# ra01m.net
KiCad netlist of a schematic drawn in Altium Designer
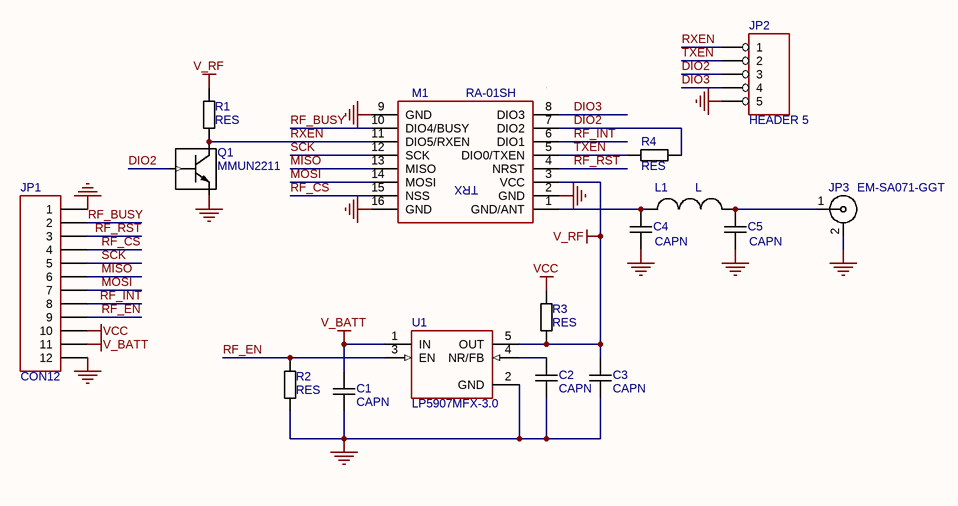
[diagram p0: ra01m.SchDoc]

(export (version "E")
  (design (tool "Eeschema 10.0.6"))
  (components
    (comp (ref "C1")
      (value "CAPN")
      (footprint "C-0805")
      (fields (field (name "VOLTAGE") "50V"))
      (libsource (lib "Passive") (part "CAPN"))
    )
    (comp (ref "C2")
      (value "CAPN")
      (footprint "C-0603")
      (fields (field (name "VOLTAGE") "50V"))
      (libsource (lib "Passive") (part "CAPN"))
    )
    (comp (ref "C3")
      (value "CAPN")
      (footprint "C-0805")
      (fields (field (name "VOLTAGE") "50V"))
      (libsource (lib "Passive") (part "CAPN"))
    )
    (comp (ref "C4")
      (value "CAPN")
      (footprint "C-0603")
      (fields (field (name "VOLTAGE") "50V"))
      (libsource (lib "Passive") (part "CAPN"))
    )
    (comp (ref "C5")
      (value "CAPN")
      (footprint "C-0603")
      (fields (field (name "VOLTAGE") "50V"))
      (libsource (lib "Passive") (part "CAPN"))
    )
    (comp (ref "JP1")
      (value "CON12")
      (footprint "PBS1-12R")
      (description "Connector")
      (libsource (lib "Connectors") (part "CON12"))
    )
    (comp (ref "JP2")
      (value "HEADER 5")
      (footprint "PLS1-5")
      (libsource (lib "Connectors") (part "HEADER 5"))
    )
    (comp (ref "JP3")
      (value "EM-SA071-GGT")
      (footprint "SMA_F_EDGE")
      (description "SMA Female R/A PCB Mount")
      (libsource (lib "Connectors") (part "SMA"))
    )
    (comp (ref "L1") (value "L") (footprint "L-0603") (libsource (lib "Passive") (part "L")))
    (comp (ref "M1")
      (value "RA-01SH")
      (footprint "RA01")
      (libsource (lib "RFmodules") (part "RA01_02_HT_RA_62"))
    )
    (comp (ref "Q1")
      (value "MMUN2211")
      (footprint "SOT-23")
      (libsource (lib "Transistors") (part "MMUN2211"))
    )
    (comp (ref "R1") (value "RES") (footprint "R-0603") (libsource (lib "Passive") (part "RES")))
    (comp (ref "R2") (value "RES") (footprint "R-0603") (libsource (lib "") (part "RES_1")))
    (comp (ref "R3") (value "RES") (footprint "R-0603") (libsource (lib "") (part "RES_1")))
    (comp (ref "R4") (value "RES") (footprint "R-0603") (libsource (lib "") (part "RES_2")))
    (comp (ref "U1")
      (value "LP5907MFX-3.0")
      (footprint "SOT-23-5")
      (description "250mA Low-Dropout Regulator")
      (libsource (lib "ICs") (part "LP5907"))
    )
  )
  (nets
    (net (code "1") (name "/DIO2") (class "Default")
      (node (ref "JP2") (pin "3") (pinfunction "3_3") (pintype "passive"))
      (node (ref "M1") (pin "7") (pinfunction "DIO2_7") (pintype "passive"))
      (node (ref "Q1") (pin "1") (pinfunction "BASE_1") (pintype "input"))
      (node (ref "R4") (pin "1") (pinfunction "1_1") (pintype "passive"))
    )
    (net (code "2") (name "/DIO3") (class "Default")
      (node (ref "JP2") (pin "4") (pinfunction "4_4") (pintype "passive"))
      (node (ref "M1") (pin "8") (pinfunction "DIO3_8") (pintype "passive"))
    )
    (net (code "3") (name "/MISO") (class "Default")
      (node (ref "JP1") (pin "6") (pinfunction "6_6") (pintype "passive"))
      (node (ref "M1") (pin "13") (pinfunction "MISO_13") (pintype "passive"))
    )
    (net (code "4") (name "/MOSI") (class "Default")
      (node (ref "JP1") (pin "7") (pinfunction "7_7") (pintype "passive"))
      (node (ref "M1") (pin "14") (pinfunction "MOSI_14") (pintype "passive"))
    )
    (net (code "5") (name "/RF_BUSY") (class "Default")
      (node (ref "JP1") (pin "2") (pinfunction "2_2") (pintype "passive"))
      (node (ref "M1") (pin "10") (pinfunction "DIO4/BUSY_10") (pintype "passive"))
    )
    (net (code "6") (name "/RF_CS") (class "Default")
      (node (ref "JP1") (pin "4") (pinfunction "4_4") (pintype "passive"))
      (node (ref "M1") (pin "15") (pinfunction "NSS_15") (pintype "passive"))
    )
    (net (code "7") (name "/RF_EN") (class "Default")
      (node (ref "JP1") (pin "9") (pinfunction "9_9") (pintype "passive"))
      (node (ref "R2") (pin "2") (pinfunction "2_2") (pintype "passive"))
      (node (ref "U1") (pin "3") (pinfunction "EN_3") (pintype "input"))
    )
    (net (code "8") (name "/RF_INT") (class "Default")
      (node (ref "JP1") (pin "8") (pinfunction "8_8") (pintype "passive"))
      (node (ref "M1") (pin "6") (pinfunction "DIO1_6") (pintype "passive"))
    )
    (net (code "9") (name "/RF_RST") (class "Default")
      (node (ref "JP1") (pin "3") (pinfunction "3_3") (pintype "passive"))
      (node (ref "M1") (pin "4") (pinfunction "NRST_4") (pintype "passive"))
    )
    (net (code "10") (name "/RXEN") (class "Default")
      (node (ref "JP2") (pin "1") (pinfunction "1_1") (pintype "passive"))
      (node (ref "M1") (pin "11") (pinfunction "DIO5/RXEN_11") (pintype "passive"))
      (node (ref "Q1") (pin "3") (pinfunction "COLLECTOR_3") (pintype "passive"))
      (node (ref "R1") (pin "2") (pinfunction "2_2") (pintype "passive"))
    )
    (net (code "11") (name "/SCK") (class "Default")
      (node (ref "JP1") (pin "5") (pinfunction "5_5") (pintype "passive"))
      (node (ref "M1") (pin "12") (pinfunction "SCK_12") (pintype "passive"))
    )
    (net (code "12") (name "/TXEN") (class "Default")
      (node (ref "JP2") (pin "2") (pinfunction "2_2") (pintype "passive"))
      (node (ref "M1") (pin "5") (pinfunction "DIO0/TXEN_5") (pintype "passive"))
      (node (ref "R4") (pin "2") (pinfunction "2_2") (pintype "passive"))
    )
    (net (code "13") (name "GND") (class "Default")
      (node (ref "C1") (pin "2") (pinfunction "2_2") (pintype "passive"))
      (node (ref "C2") (pin "2") (pinfunction "2_2") (pintype "passive"))
      (node (ref "C3") (pin "2") (pinfunction "2_2") (pintype "passive"))
      (node (ref "C4") (pin "2") (pinfunction "2_2") (pintype "passive"))
      (node (ref "C5") (pin "2") (pinfunction "2_2") (pintype "passive"))
      (node (ref "JP1") (pin "1") (pinfunction "1_1") (pintype "passive"))
      (node (ref "JP1") (pin "12") (pinfunction "12_12") (pintype "passive"))
      (node (ref "JP2") (pin "5") (pinfunction "5_5") (pintype "passive"))
      (node (ref "JP3") (pin "2") (pinfunction "2_2") (pintype "passive"))
      (node (ref "M1") (pin "16") (pinfunction "GND_16") (pintype "passive"))
      (node (ref "M1") (pin "2") (pinfunction "GND_2") (pintype "passive"))
      (node (ref "M1") (pin "9") (pinfunction "GND_9") (pintype "passive"))
      (node (ref "Q1") (pin "2") (pinfunction "EMITTER_2") (pintype "passive"))
      (node (ref "R2") (pin "1") (pinfunction "1_1") (pintype "passive"))
      (node (ref "U1") (pin "2") (pinfunction "GND_2") (pintype "power_in"))
    )
    (net (code "14") (name "Net-(C5-Pad1)") (class "Default")
      (node (ref "C5") (pin "1") (pinfunction "1_1") (pintype "passive"))
      (node (ref "JP3") (pin "1") (pinfunction "1_1") (pintype "passive"))
      (node (ref "L1") (pin "2") (pinfunction "2_2") (pintype "passive"))
    )
    (net (code "15") (name "Net-(M1-GND{slash}ANT)") (class "Default")
      (node (ref "C4") (pin "1") (pinfunction "1_1") (pintype "passive"))
      (node (ref "L1") (pin "1") (pinfunction "1_1") (pintype "passive"))
      (node (ref "M1") (pin "1") (pinfunction "GND/ANT_1") (pintype "passive"))
    )
    (net (code "16") (name "Net-(U1-NR{slash}FB)") (class "Default")
      (node (ref "C2") (pin "1") (pinfunction "1_1") (pintype "passive"))
      (node (ref "U1") (pin "4") (pinfunction "NR/FB_4") (pintype "input"))
    )
    (net (code "17") (name "VCC") (class "Default")
      (node (ref "JP1") (pin "10") (pinfunction "10_10") (pintype "passive"))
      (node (ref "R3") (pin "2") (pinfunction "2_2") (pintype "passive"))
    )
    (net (code "18") (name "V_BATT") (class "Default")
      (node (ref "C1") (pin "1") (pinfunction "1_1") (pintype "passive"))
      (node (ref "JP1") (pin "11") (pinfunction "11_11") (pintype "passive"))
      (node (ref "U1") (pin "1") (pinfunction "IN_1") (pintype "power_in"))
    )
    (net (code "19") (name "V_RF") (class "Default")
      (node (ref "C3") (pin "1") (pinfunction "1_1") (pintype "passive"))
      (node (ref "M1") (pin "3") (pinfunction "VCC_3") (pintype "passive"))
      (node (ref "R1") (pin "1") (pinfunction "1_1") (pintype "passive"))
      (node (ref "R3") (pin "1") (pinfunction "1_1") (pintype "passive"))
      (node (ref "U1") (pin "5") (pinfunction "OUT_5") (pintype "power_in"))
    )
  )
)
